# 07_-_USB_Interface.net
KiCad netlist of a schematic drawn in Altium Designer
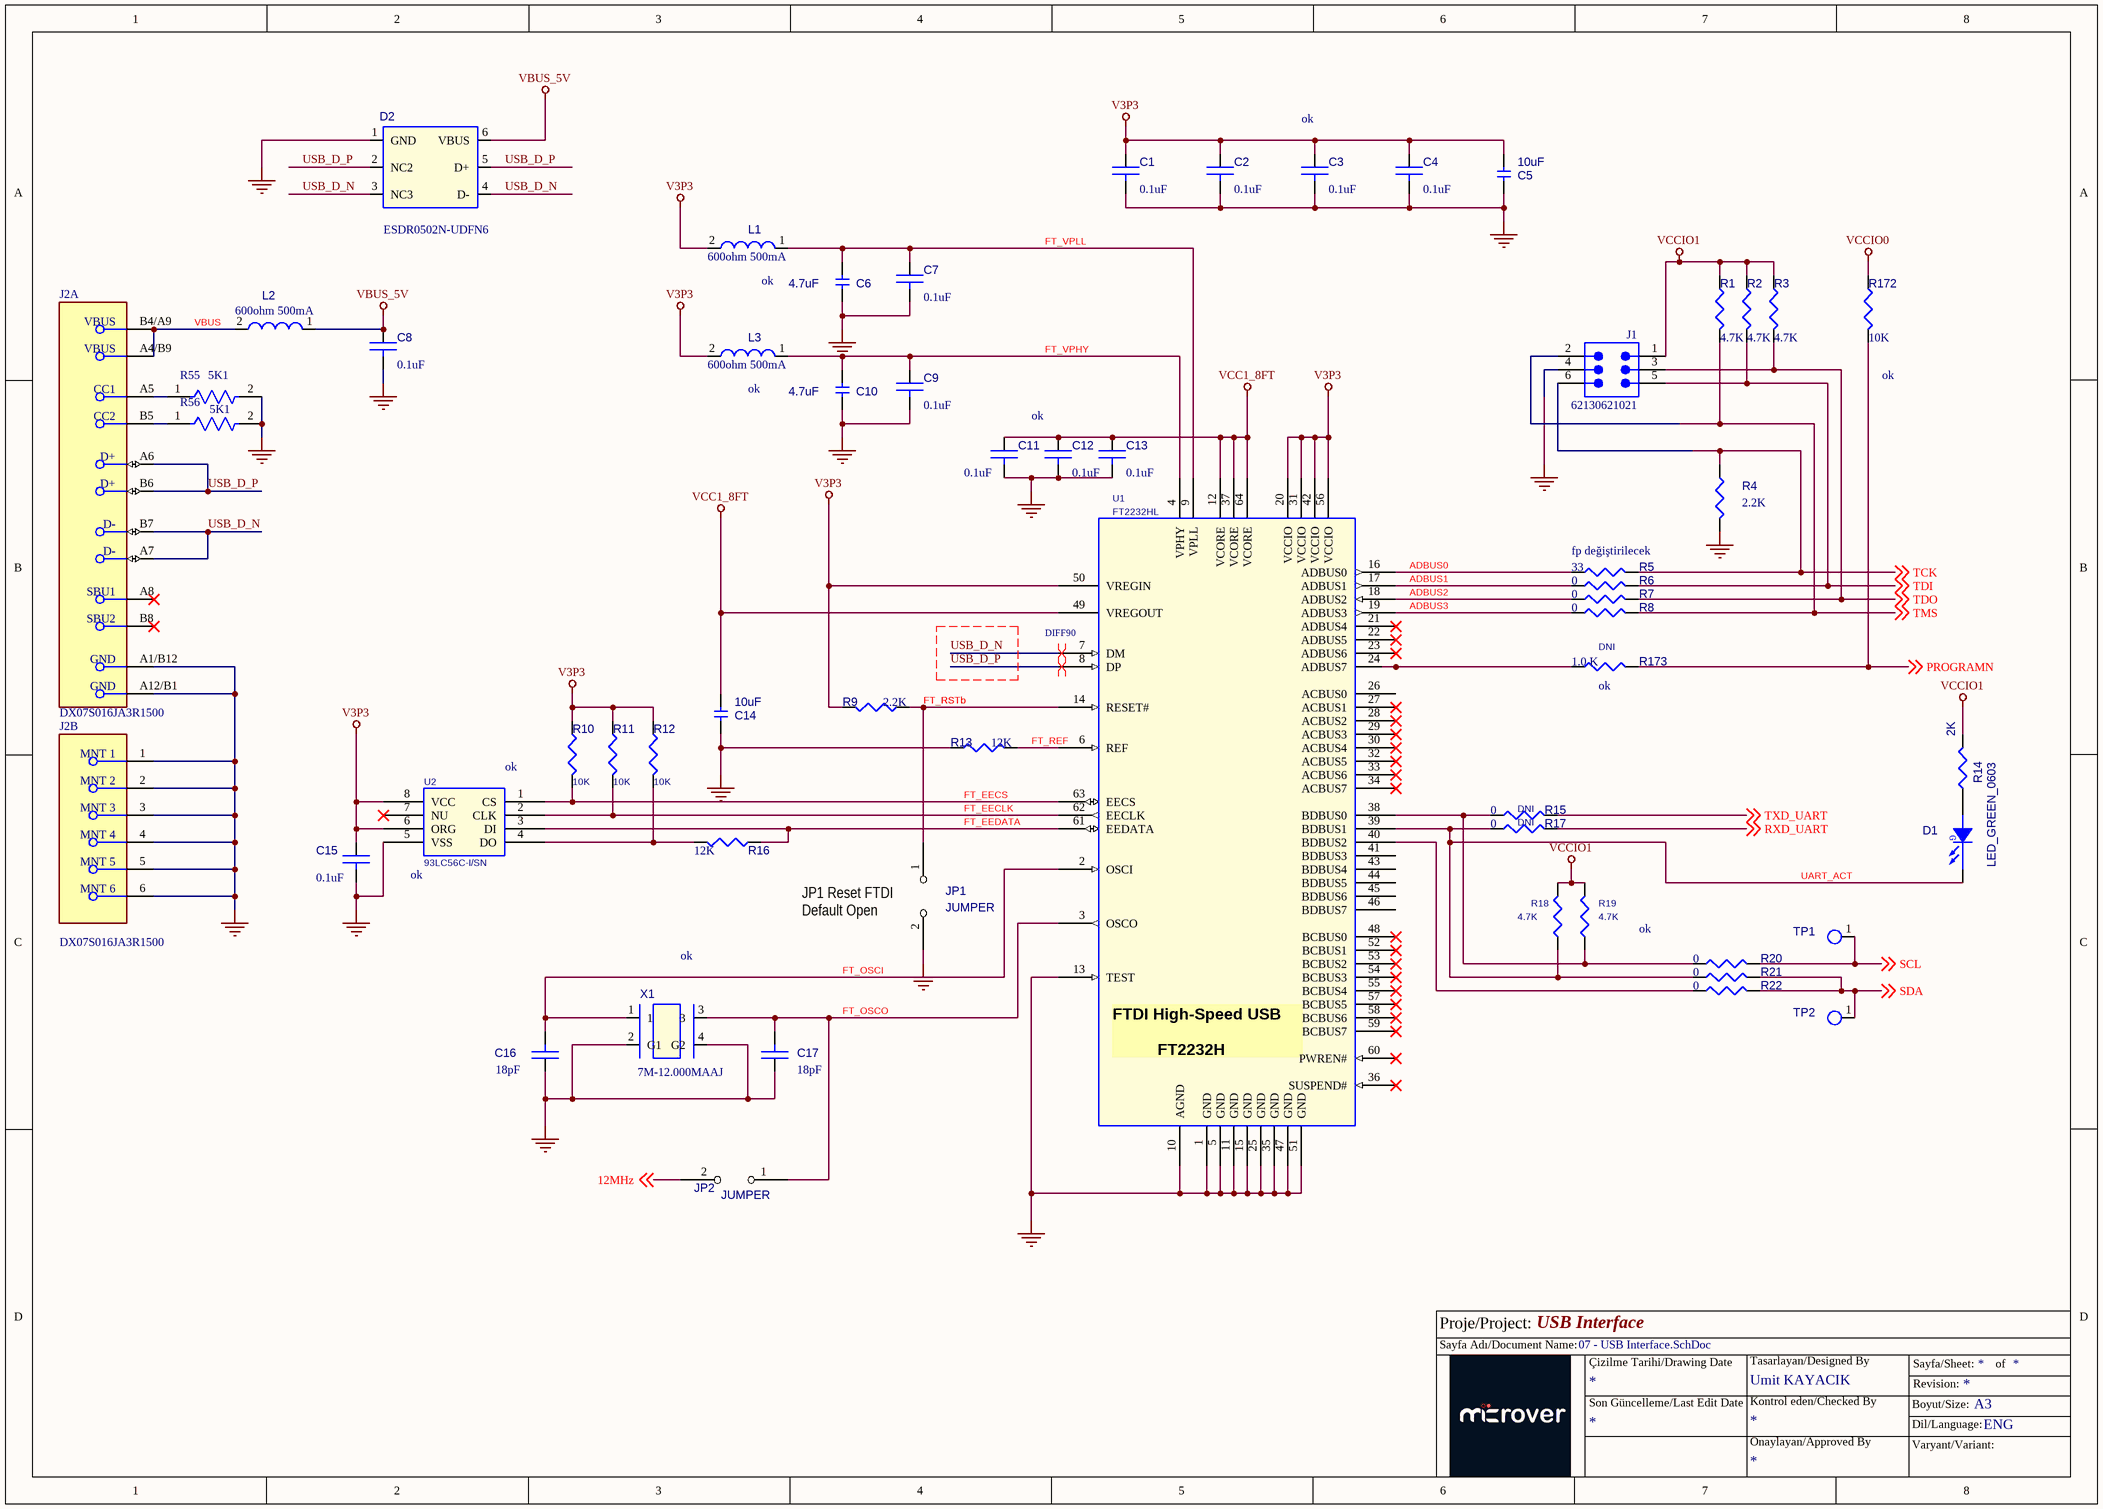
[diagram p0: 07 - USB Interface.SchDoc]

(export (version "E")
  (design (tool "Eeschema 10.0.6"))
  (components
    (comp (ref "C1")
      (value "0.1uF")
      (footprint "C0201")
      (description "CAP CER 0.1UF 25V 10% X5R 0201")
      (fields
        (field (name "MANUFACTURER") "Murata")
        (field (name "MANUFACTURER PART NUMBER") "GRM033R61E104KE14J")
      )
      (libsource (lib "*") (part "0u1_0402"))
    )
    (comp (ref "C2")
      (value "0.1uF")
      (footprint "C0201")
      (description "CAP CER 0.1UF 25V 10% X5R 0201")
      (fields
        (field (name "MANUFACTURER") "Murata")
        (field (name "MANUFACTURER PART NUMBER") "GRM033R61E104KE14J")
      )
      (libsource (lib "*") (part "0u1_0402"))
    )
    (comp (ref "C3")
      (value "0.1uF")
      (footprint "C0201")
      (description "CAP CER 0.1UF 25V 10% X5R 0201")
      (fields
        (field (name "MANUFACTURER") "Murata")
        (field (name "MANUFACTURER PART NUMBER") "GRM033R61E104KE14J")
      )
      (libsource (lib "*") (part "0u1_0402"))
    )
    (comp (ref "C4")
      (value "0.1uF")
      (footprint "C0201")
      (description "CAP CER 0.1UF 25V 10% X5R 0201")
      (fields
        (field (name "MANUFACTURER") "Murata")
        (field (name "MANUFACTURER PART NUMBER") "GRM033R61E104KE14J")
      )
      (libsource (lib "*") (part "0u1_0402"))
    )
    (comp (ref "C5")
      (value "10uF")
      (footprint "C0603")
      (fields (field (name "VOLTAGE") "CMAX"))
      (libsource (lib "*") (part "C"))
    )
    (comp (ref "C6")
      (value "4.7uF")
      (footprint "C0603")
      (fields (field (name "VOLTAGE") "CMAX"))
      (libsource (lib "*") (part "C"))
    )
    (comp (ref "C7")
      (value "0.1uF")
      (footprint "C0201")
      (description "CAP CER 0.1UF 25V 10% X5R 0201")
      (fields
        (field (name "MANUFACTURER") "Murata")
        (field (name "MANUFACTURER PART NUMBER") "GRM033R61E104KE14J")
      )
      (libsource (lib "*") (part "0u1_0402"))
    )
    (comp (ref "C8")
      (value "0.1uF")
      (footprint "C0402")
      (description "CAP CER 0.1UF 25V 10% X5R 0201")
      (fields
        (field (name "MANUFACTURER") "Murata")
        (field (name "MANUFACTURER PART NUMBER") "GRM033R61E104KE14J")
      )
      (libsource (lib "*") (part "0u1_0402"))
    )
    (comp (ref "C9")
      (value "0.1uF")
      (footprint "C0201")
      (description "CAP CER 0.1UF 25V 10% X5R 0201")
      (fields
        (field (name "MANUFACTURER") "Murata")
        (field (name "MANUFACTURER PART NUMBER") "GRM033R61E104KE14J")
      )
      (libsource (lib "*") (part "0u1_0402"))
    )
    (comp (ref "C10")
      (value "4.7uF")
      (footprint "C0603")
      (fields (field (name "VOLTAGE") "CMAX"))
      (libsource (lib "*") (part "C"))
    )
    (comp (ref "C11")
      (value "0.1uF")
      (footprint "C0201")
      (description "CAP CER 0.1UF 25V 10% X5R 0201")
      (fields
        (field (name "MANUFACTURER") "Murata")
        (field (name "MANUFACTURER PART NUMBER") "GRM033R61E104KE14J")
      )
      (libsource (lib "*") (part "0u1_0402"))
    )
    (comp (ref "C12")
      (value "0.1uF")
      (footprint "C0201")
      (description "CAP CER 0.1UF 25V 10% X5R 0201")
      (fields
        (field (name "MANUFACTURER") "Murata")
        (field (name "MANUFACTURER PART NUMBER") "GRM033R61E104KE14J")
      )
      (libsource (lib "*") (part "0u1_0402"))
    )
    (comp (ref "C13")
      (value "0.1uF")
      (footprint "c0201")
      (description "CAP CER 0.1UF 25V 10% X5R 0201")
      (fields
        (field (name "MANUFACTURER") "Murata")
        (field (name "MANUFACTURER PART NUMBER") "GRM033R61E104KE14J")
      )
      (libsource (lib "*") (part "0u1_0402"))
    )
    (comp (ref "C14")
      (value "10uF")
      (footprint "C0603")
      (fields (field (name "VOLTAGE") "CMAX"))
      (libsource (lib "*") (part "C"))
    )
    (comp (ref "C15")
      (value "0.1uF")
      (footprint "C0201")
      (description "CAP CER 0.1UF 25V 10% X5R 0201")
      (fields
        (field (name "MANUFACTURER") "Murata")
        (field (name "MANUFACTURER PART NUMBER") "GRM033R61E104KE14J")
      )
      (libsource (lib "*") (part "0u1_0402"))
    )
    (comp (ref "C16")
      (value "18pF")
      (footprint "C0402")
      (description "CAP CER 18PF 25V 10% NP0 0402")
      (fields
        (field (name "MANUFACTURER") "Kemet")
        (field (name "MANUFACTURER PART NUMBER") "C0402C180K3GACTU")
      )
      (libsource (lib "*") (part "0u1_0402"))
    )
    (comp (ref "C17")
      (value "18pF")
      (footprint "C0402")
      (description "CAP CER 18PF 25V 10% NP0 0402")
      (fields
        (field (name "MANUFACTURER") "Kemet")
        (field (name "MANUFACTURER PART NUMBER") "C0402C180K3GACTU")
      )
      (libsource (lib "*") (part "0u1_0402"))
    )
    (comp (ref "D1")
      (value "LED_GREEN_0603")
      (footprint "APT1608")
      (libsource (lib "*") (part "LED-SMT1206_GREEN_1"))
    )
    (comp (ref "D2")
      (value "ESDR0502N-UDFN6")
      (footprint "UDFN6_040")
      (description "ESD Protection - SLP2510P8 package 8-PIN")
      (fields (field (name "MFG") "Semtech"))
      (libsource (lib "*") (part "ESDR0502"))
    )
    (comp (ref "J1")
      (value "62130621021")
      (footprint "62130621021")
      (description "Conn, Pin Hdr, 6POS, 2ROW, 1.27MM Rohs Compliant: Yes")
      (libsource (lib "Altium Content Vault") (part "Header_Male_2R_06P"))
    )
    (comp (ref "J2")
      (value "DX07S016JA3R1500")
      (footprint "FP-DX07S016JA3R1500-MFG")
      (description "CONN RCP USB2.0 TYP C 24P SMD RA")
      (libsource (lib "Altium Content Vault") (part "86c7019cab7ffbad937e454fd6d8a8a"))
    )
    (comp (ref "JP1") (value "JUMPER") (footprint "R0603") (libsource (lib "*") (part "JUMPER_0")))
    (comp (ref "JP2") (value "JUMPER") (footprint "0603") (libsource (lib "*") (part "JUMPER_0")))
    (comp (ref "L1")
      (value "600ohm 500mA")
      (footprint "FB0603")
      (description "FERRITE CHIP 600 OHM 500MA 0603")
      (fields
        (field (name "MANUFACTURER") "Murata")
        (field (name "MANUFACTURER PART NUMBER") "BLM18AG601SN1D")
      )
      (libsource (lib "*") (part "FB0603"))
    )
    (comp (ref "L2")
      (value "600ohm 500mA")
      (footprint "FB0603")
      (description "FERRITE CHIP 600 OHM 500MA 0603")
      (fields
        (field (name "MANUFACTURER") "Murata")
        (field (name "MANUFACTURER PART NUMBER") "BLM18AG601SN1D")
      )
      (libsource (lib "*") (part "FB0603"))
    )
    (comp (ref "L3")
      (value "600ohm 500mA")
      (footprint "FB0603")
      (description "FERRITE CHIP 600 OHM 500MA 0603")
      (fields
        (field (name "MANUFACTURER") "Murata")
        (field (name "MANUFACTURER PART NUMBER") "BLM18AG601SN1D")
      )
      (libsource (lib "*") (part "FB0603"))
    )
    (comp (ref "R1")
      (value "4.7K")
      (footprint "R0603")
      (description "RES 4.70K OHM 1/10W 1% 0603 SMD")
      (fields
        (field (name "MANUFACTURER PART NUMBER") "CRCW06034K70FKEA")
        (field (name "MANUFACTURER") "Vishay")
      )
      (libsource (lib "*") (part "5k1_0402"))
    )
    (comp (ref "R2")
      (value "4.7K")
      (footprint "R0603")
      (description "RES 4.70K OHM 1/10W 1% 0603 SMD")
      (fields
        (field (name "MANUFACTURER PART NUMBER") "CRCW06034K70FKEA")
        (field (name "MANUFACTURER") "Vishay")
      )
      (libsource (lib "*") (part "5k1_0402"))
    )
    (comp (ref "R3")
      (value "4.7K")
      (footprint "R0603")
      (description "RES 4.70K OHM 1/10W 1% 0603 SMD")
      (fields
        (field (name "MANUFACTURER PART NUMBER") "CRCW06034K70FKEA")
        (field (name "MANUFACTURER") "Vishay")
      )
      (libsource (lib "*") (part "5k1_0402"))
    )
    (comp (ref "R4")
      (value "2.2K")
      (footprint "R0603")
      (fields
        (field (name "MANUFACTURER PART NUMBER") "CRCW06032K20FKEA")
        (field (name "MANUFACTURER") "Vishay")
      )
      (libsource (lib "*") (part "5k1_0402"))
    )
    (comp (ref "R5")
      (value "33")
      (footprint "R0402")
      (description "RES SMD 33 OHM 1% 1/10W 0402")
      (fields
        (field (name "MANUFACTURER") "Panasonic")
        (field (name "MANUFACTURER PART NUMBER") "ERJ-2RKF33R0X")
      )
      (libsource (lib "*") (part "0R_0603"))
    )
    (comp (ref "R6")
      (value "0")
      (footprint "R0603")
      (description "RES 0.0 OHM 1/10W JUMP 0603 SMD")
      (fields
        (field (name "MANUFACTURER") "Yageo")
        (field (name "MANUFACTURER PART NUMBER") "RC0603JR-070RL")
      )
      (libsource (lib "*") (part "0R_0603"))
    )
    (comp (ref "R7")
      (value "0")
      (footprint "R0603")
      (description "RES 0.0 OHM 1/10W JUMP 0603 SMD")
      (fields
        (field (name "MANUFACTURER") "Yageo")
        (field (name "MANUFACTURER PART NUMBER") "RC0603JR-070RL")
      )
      (libsource (lib "*") (part "0R_0603"))
    )
    (comp (ref "R8")
      (value "0")
      (footprint "R0603")
      (description "RES 0.0 OHM 1/10W JUMP 0603 SMD")
      (fields
        (field (name "MANUFACTURER") "Yageo")
        (field (name "MANUFACTURER PART NUMBER") "RC0603JR-070RL")
      )
      (libsource (lib "*") (part "0R_0603"))
    )
    (comp (ref "R9")
      (value "2.2K")
      (footprint "R0603")
      (fields
        (field (name "MANUFACTURER PART NUMBER") "CRCW06032K20FKEA")
        (field (name "MANUFACTURER") "Vishay")
      )
      (libsource (lib "*") (part "5k1_0402"))
    )
    (comp (ref "R10")
      (value "10K")
      (footprint "R0603")
      (description "RES 10K OHM 1/10W 5% 0603")
      (fields
        (field (name "MFG") "Stackpole Electronics Inc")
        (field (name "MANUFACTURER PART NUMBER") "RMCF0603JT10K0")
      )
      (libsource (lib "*") (part "RES_10K_1W16_0402_5P"))
    )
    (comp (ref "R11")
      (value "10K")
      (footprint "R0603")
      (description "RES 10K OHM 1/10W 5% 0603")
      (fields
        (field (name "MFG") "Stackpole Electronics Inc")
        (field (name "MANUFACTURER PART NUMBER") "RMCF0603JT10K0")
      )
      (libsource (lib "*") (part "RES_10K_1W16_0402_5P"))
    )
    (comp (ref "R12")
      (value "10K")
      (footprint "R0603")
      (description "RES 10K OHM 1/10W 5% 0603")
      (fields
        (field (name "MFG") "Stackpole Electronics Inc")
        (field (name "MANUFACTURER PART NUMBER") "RMCF0603JT10K0")
      )
      (libsource (lib "*") (part "RES_10K_1W16_0402_5P"))
    )
    (comp (ref "R13")
      (value "12K")
      (footprint "R0603")
      (description "RES 12K OHM 1/10W 1% 0603 SMD")
      (fields
        (field (name "MANUFACTURER") "Yageo")
        (field (name "MANUFACTURER PART NUMBER") "RC0603FR-0712KL")
      )
      (libsource (lib "*") (part "10k_0402"))
    )
    (comp (ref "R14") (value "2K") (footprint "R0402") (libsource (lib "*") (part "RES_0")))
    (comp (ref "R15")
      (value "0")
      (footprint "R0603")
      (description "Res 1/10W 0.0 Ohm 5% 0603")
      (fields
        (field (name "MANUFACTURER") "Yageo")
        (field (name "MANUFACTURER PART NUMBER") "RC0603JR-070RL")
        (field (name "ASSY") "DNI")
      )
      (libsource (lib "*") (part "0R_0603"))
    )
    (comp (ref "R16")
      (value "12K")
      (footprint "R0603")
      (description "RES 12K OHM 1/10W 1% 0603 SMD")
      (fields
        (field (name "MANUFACTURER") "Yageo")
        (field (name "MANUFACTURER PART NUMBER") "RC0603FR-0712KL")
      )
      (libsource (lib "*") (part "10k_0402"))
    )
    (comp (ref "R17")
      (value "0")
      (footprint "R0603")
      (description "Res 1/10W 0.0 Ohm 5% 0603")
      (fields
        (field (name "MANUFACTURER") "Yageo")
        (field (name "MANUFACTURER PART NUMBER") "RC0603JR-070RL")
        (field (name "ASSY") "DNI")
      )
      (libsource (lib "*") (part "0R_0603"))
    )
    (comp (ref "R18") (value "4.7K") (footprint "RLP-101") (libsource (lib "*") (part "RESISTOR")))
    (comp (ref "R19") (value "4.7K") (footprint "RLP-101") (libsource (lib "*") (part "RESISTOR")))
    (comp (ref "R20")
      (value "0")
      (footprint "R0603")
      (description "RES 0.0 OHM 1/10W JUMP 0603 SMD")
      (fields
        (field (name "MANUFACTURER") "Yageo")
        (field (name "MANUFACTURER PART NUMBER") "RC0603JR-070RL")
      )
      (libsource (lib "*") (part "0R_0603"))
    )
    (comp (ref "R21")
      (value "0")
      (footprint "R0603")
      (description "RES 0.0 OHM 1/10W JUMP 0603 SMD")
      (fields
        (field (name "MANUFACTURER") "Yageo")
        (field (name "MANUFACTURER PART NUMBER") "RC0603JR-070RL")
      )
      (libsource (lib "*") (part "0R_0603"))
    )
    (comp (ref "R22")
      (value "0")
      (footprint "R0603")
      (description "RES 0.0 OHM 1/10W JUMP 0603 SMD")
      (fields
        (field (name "MANUFACTURER") "Yageo")
        (field (name "MANUFACTURER PART NUMBER") "RC0603JR-070RL")
      )
      (libsource (lib "*") (part "0R_0603"))
    )
    (comp (ref "R55")
      (value "5K1")
      (footprint "FP-CR0402-IPC_A")
      (description "Thick Film Chip Resistors 0402 5.1kΩ 0.0625W 1% 100ppm/°C")
      (fields (field (name "TOLERANCE") "1%"))
      (libsource (lib "Altium Content Vault") (part "1029c3af85768c4190bb7ad29bc67b5"))
    )
    (comp (ref "R56")
      (value "5K1")
      (footprint "FP-CR0402-IPC_A")
      (description "Thick Film Chip Resistors 0402 5.1kΩ 0.0625W 1% 100ppm/°C")
      (fields (field (name "TOLERANCE") "1%"))
      (libsource (lib "Altium Content Vault") (part "1029c3af85768c4190bb7ad29bc67b5"))
    )
    (comp (ref "R172")
      (value "10K")
      (footprint "R0603")
      (description "RES SMD 10K OHM 1% 1/10W 0603")
      (fields
        (field (name "MANUFACTURER PART NUMBER") "RC0603FR-0710KL")
        (field (name "MANUFACTURER") "Yageo")
      )
      (libsource (lib "*") (part "5k1_0402"))
    )
    (comp (ref "R173")
      (value "1.0 K")
      (footprint "R0603")
      (description "RES SMD 1K OHM 1% 1/10W 0603")
      (fields
        (field (name "MANUFACTURER") "Yageo")
        (field (name "MANUFACTURER PART NUMBER") "RC0603FR-071KL")
        (field (name "ASSY") "DNI")
      )
      (libsource (lib "*") (part "0R_0603"))
    )
    (comp (ref "TP1")
      (value "TP_S_40_63")
      (footprint "TP_1MM")
      (description "Square test point, 40mil inner diameter, 63mil outer diameter")
      (libsource (lib "*") (part "TP_S_40_63"))
    )
    (comp (ref "TP2")
      (value "TP_S_40_63")
      (footprint "TP_1MM")
      (description "Square test point, 40mil inner diameter, 63mil outer diameter")
      (libsource (lib "*") (part "TP_S_40_63"))
    )
    (comp (ref "U1")
      (value "FT2232HL")
      (footprint "tqfp64_0p5_12p2x12p2_h1p6")
      (description "IC USB HS DUAL UART/FIFO 64-LQFP")
      (fields (field (name "MANUFACTURER") "FTDI"))
      (libsource (lib "*") (part "FT2232HL"))
    )
    (comp (ref "U2")
      (value "93LC56C-I/SN")
      (footprint "so8_50_244")
      (description "IC EEPROM 2KBIT 3MHZ 8SOIC")
      (fields (field (name "MANUFACTURER") "Microchip"))
      (libsource (lib "*") (part "93LC56_SO8_0"))
    )
    (comp (ref "X1")
      (value "7M-12.000MAAJ")
      (footprint "xtal_4p_7m")
      (description "CRYSTAL 12MHZ 18PF SMD")
      (fields (field (name "MANUFACTURER PART NUMBER") "7M-12.000MAAJ-T") (field (name "MANUFACTURER") "TXC"))
      (libsource (lib "*") (part "crystal-3p2x2p5"))
    )
  )
  (nets
    (net (code "1") (name "/ADBUS0") (class "Default")
      (node (ref "R5") (pin "1") (pinfunction "1_1") (pintype "passive"))
      (node (ref "U1") (pin "16") (pinfunction "ADBUS0_16") (pintype "output"))
    )
    (net (code "2") (name "/ADBUS1") (class "Default")
      (node (ref "R6") (pin "1") (pinfunction "1_1") (pintype "passive"))
      (node (ref "U1") (pin "17") (pinfunction "ADBUS1_17") (pintype "output"))
    )
    (net (code "3") (name "/ADBUS2") (class "Default")
      (node (ref "R7") (pin "1") (pinfunction "1_1") (pintype "passive"))
      (node (ref "U1") (pin "18") (pinfunction "ADBUS2_18") (pintype "input"))
    )
    (net (code "4") (name "/ADBUS3") (class "Default")
      (node (ref "R8") (pin "1") (pinfunction "1_1") (pintype "passive"))
      (node (ref "U1") (pin "19") (pinfunction "ADBUS3_19") (pintype "output"))
    )
    (net (code "5") (name "/FT_EECLK") (class "Default")
      (node (ref "R11") (pin "2") (pinfunction "2_2") (pintype "passive"))
      (node (ref "U1") (pin "62") (pinfunction "EECLK_62") (pintype "output"))
      (node (ref "U2") (pin "2") (pinfunction "CLK_2") (pintype "passive"))
    )
    (net (code "6") (name "/FT_EECS") (class "Default")
      (node (ref "R10") (pin "2") (pinfunction "2_2") (pintype "passive"))
      (node (ref "U1") (pin "63") (pinfunction "EECS_63") (pintype "bidirectional"))
      (node (ref "U2") (pin "1") (pinfunction "CS_1") (pintype "passive"))
    )
    (net (code "7") (name "/FT_EEDATA") (class "Default")
      (node (ref "R16") (pin "1") (pinfunction "1_1") (pintype "passive"))
      (node (ref "U1") (pin "61") (pinfunction "EEDATA_61") (pintype "bidirectional"))
      (node (ref "U2") (pin "3") (pinfunction "DI_3") (pintype "passive"))
    )
    (net (code "8") (name "/FT_OSCI") (class "Default")
      (node (ref "C16") (pin "2") (pinfunction "2_2") (pintype "passive"))
      (node (ref "U1") (pin "2") (pinfunction "OSCI_2") (pintype "input"))
      (node (ref "X1") (pin "1") (pinfunction "1_1") (pintype "passive"))
    )
    (net (code "9") (name "/FT_OSCO") (class "Default")
      (node (ref "C17") (pin "2") (pinfunction "2_2") (pintype "passive"))
      (node (ref "JP2") (pin "1") (pinfunction "1_1") (pintype "passive"))
      (node (ref "U1") (pin "3") (pinfunction "OSCO_3") (pintype "output"))
      (node (ref "X1") (pin "3") (pinfunction "3_3") (pintype "passive"))
    )
    (net (code "10") (name "/FT_REF") (class "Default")
      (node (ref "R13") (pin "2") (pinfunction "2_2") (pintype "passive"))
      (node (ref "U1") (pin "6") (pinfunction "REF_6") (pintype "input"))
    )
    (net (code "11") (name "/FT_RSTb") (class "Default")
      (node (ref "JP1") (pin "1") (pinfunction "1_1") (pintype "passive"))
      (node (ref "R9") (pin "1") (pinfunction "1_1") (pintype "passive"))
      (node (ref "U1") (pin "14") (pinfunction "RESET#_14") (pintype "input"))
    )
    (net (code "12") (name "/FT_VPHY") (class "Default")
      (node (ref "C10") (pin "2") (pinfunction "2_2") (pintype "passive"))
      (node (ref "C9") (pin "1") (pinfunction "1_1") (pintype "passive"))
      (node (ref "L3") (pin "1") (pinfunction "1_1") (pintype "passive"))
      (node (ref "U1") (pin "4") (pinfunction "VPHY_4") (pintype "power_in"))
    )
    (net (code "13") (name "/FT_VPLL") (class "Default")
      (node (ref "C6") (pin "2") (pinfunction "2_2") (pintype "passive"))
      (node (ref "C7") (pin "1") (pinfunction "1_1") (pintype "passive"))
      (node (ref "L1") (pin "1") (pinfunction "1_1") (pintype "passive"))
      (node (ref "U1") (pin "9") (pinfunction "VPLL_9") (pintype "power_in"))
    )
    (net (code "14") (name "/UART_ACT") (class "Default")
      (node (ref "D1") (pin "1") (pinfunction "CATHODE_1") (pintype "passive"))
      (node (ref "R17") (pin "1") (pinfunction "1_1") (pintype "passive"))
      (node (ref "R18") (pin "1") (pinfunction "1_1") (pintype "passive"))
      (node (ref "R21") (pin "1") (pinfunction "1_1") (pintype "passive"))
      (node (ref "U1") (pin "39") (pinfunction "BDBUS1_39") (pintype "passive"))
    )
    (net (code "15") (name "/USB_D_N") (class "Default")
      (node (ref "D2") (pin "3") (pinfunction "NC3_3") (pintype "passive"))
      (node (ref "D2") (pin "4") (pinfunction "D-_4") (pintype "passive"))
      (node (ref "J2") (pin "A7") (pinfunction "D-_A7") (pintype "bidirectional"))
      (node (ref "J2") (pin "B7") (pinfunction "D-_B7") (pintype "bidirectional"))
      (node (ref "U1") (pin "7") (pinfunction "DM_7") (pintype "input"))
    )
    (net (code "16") (name "/USB_D_P") (class "Default")
      (node (ref "D2") (pin "2") (pinfunction "NC2_2") (pintype "passive"))
      (node (ref "D2") (pin "5") (pinfunction "D+_5") (pintype "passive"))
      (node (ref "J2") (pin "A6") (pinfunction "D+_A6") (pintype "bidirectional"))
      (node (ref "J2") (pin "B6") (pinfunction "D+_B6") (pintype "bidirectional"))
      (node (ref "U1") (pin "8") (pinfunction "DP_8") (pintype "input"))
    )
    (net (code "17") (name "/VBUS") (class "Default")
      (node (ref "J2") (pin "A4/B9") (pinfunction "VBUS_A4/B9") (pintype "power_in"))
      (node (ref "J2") (pin "B4/A9") (pinfunction "VBUS_B4/A9") (pintype "power_in"))
      (node (ref "L2") (pin "2") (pinfunction "2_2") (pintype "passive"))
    )
    (net (code "18") (name "12MHz") (class "Default")
      (node (ref "JP2") (pin "2") (pinfunction "2_2") (pintype "passive"))
    )
    (net (code "19") (name "GND") (class "Default")
      (node (ref "C1") (pin "2") (pinfunction "2_2") (pintype "passive"))
      (node (ref "C10") (pin "1") (pinfunction "1_1") (pintype "passive"))
      (node (ref "C11") (pin "2") (pinfunction "2_2") (pintype "passive"))
      (node (ref "C12") (pin "2") (pinfunction "2_2") (pintype "passive"))
      (node (ref "C13") (pin "2") (pinfunction "2_2") (pintype "passive"))
      (node (ref "C14") (pin "1") (pinfunction "1_1") (pintype "passive"))
      (node (ref "C15") (pin "2") (pinfunction "2_2") (pintype "passive"))
      (node (ref "C16") (pin "1") (pinfunction "1_1") (pintype "passive"))
      (node (ref "C17") (pin "1") (pinfunction "1_1") (pintype "passive"))
      (node (ref "C2") (pin "2") (pinfunction "2_2") (pintype "passive"))
      (node (ref "C3") (pin "2") (pinfunction "2_2") (pintype "passive"))
      (node (ref "C4") (pin "2") (pinfunction "2_2") (pintype "passive"))
      (node (ref "C5") (pin "1") (pinfunction "1_1") (pintype "passive"))
      (node (ref "C6") (pin "1") (pinfunction "1_1") (pintype "passive"))
      (node (ref "C7") (pin "2") (pinfunction "2_2") (pintype "passive"))
      (node (ref "C8") (pin "2") (pinfunction "2_2") (pintype "passive"))
      (node (ref "C9") (pin "2") (pinfunction "2_2") (pintype "passive"))
      (node (ref "D2") (pin "1") (pinfunction "GND_1") (pintype "passive"))
      (node (ref "J1") (pin "4") (pinfunction "4_4") (pintype "passive"))
      (node (ref "J2") (pin "1") (pinfunction "MNT_1_1") (pintype "passive"))
      (node (ref "J2") (pin "2") (pinfunction "MNT_2_2") (pintype "passive"))
      (node (ref "J2") (pin "3") (pinfunction "MNT_3_3") (pintype "passive"))
      (node (ref "J2") (pin "4") (pinfunction "MNT_4_4") (pintype "passive"))
      (node (ref "J2") (pin "5") (pinfunction "MNT_5_5") (pintype "passive"))
      (node (ref "J2") (pin "6") (pinfunction "MNT_6_6") (pintype "passive"))
      (node (ref "J2") (pin "A1/B12") (pinfunction "GND_A1/B12") (pintype "power_in"))
      (node (ref "J2") (pin "A12/B1") (pinfunction "GND_A12/B1") (pintype "power_in"))
      (node (ref "JP1") (pin "2") (pinfunction "2_2") (pintype "passive"))
      (node (ref "R13") (pin "1") (pinfunction "1_1") (pintype "passive"))
      (node (ref "R4") (pin "2") (pinfunction "2_2") (pintype "passive"))
      (node (ref "R55") (pin "2") (pinfunction "2_2") (pintype "passive"))
      (node (ref "R56") (pin "2") (pinfunction "2_2") (pintype "passive"))
      (node (ref "U1") (pin "1") (pinfunction "GND_1") (pintype "power_in"))
      (node (ref "U1") (pin "10") (pinfunction "AGND_10") (pintype "power_in"))
      (node (ref "U1") (pin "11") (pinfunction "GND_11") (pintype "power_in"))
      (node (ref "U1") (pin "13") (pinfunction "TEST_13") (pintype "input"))
      (node (ref "U1") (pin "15") (pinfunction "GND_15") (pintype "power_in"))
      (node (ref "U1") (pin "25") (pinfunction "GND_25") (pintype "power_in"))
      (node (ref "U1") (pin "35") (pinfunction "GND_35") (pintype "power_in"))
      (node (ref "U1") (pin "47") (pinfunction "GND_47") (pintype "power_in"))
      (node (ref "U1") (pin "5") (pinfunction "GND_5") (pintype "power_in"))
      (node (ref "U1") (pin "51") (pinfunction "GND_51") (pintype "power_in"))
      (node (ref "U2") (pin "5") (pinfunction "VSS_5") (pintype "power_in"))
      (node (ref "X1") (pin "2") (pinfunction "G1_2") (pintype "passive"))
      (node (ref "X1") (pin "4") (pinfunction "G2_4") (pintype "passive"))
    )
    (net (code "20") (name "Net-(D1-ANODE)") (class "Default")
      (node (ref "D1") (pin "2") (pinfunction "ANODE_2") (pintype "passive"))
      (node (ref "R14") (pin "1") (pinfunction "1_1") (pintype "passive"))
    )
    (net (code "21") (name "Net-(J2A-CC1)") (class "Default")
      (node (ref "J2") (pin "A5") (pinfunction "CC1_A5") (pintype "passive"))
      (node (ref "R55") (pin "1") (pinfunction "1_1") (pintype "passive"))
    )
    (net (code "22") (name "Net-(J2A-CC2)") (class "Default")
      (node (ref "J2") (pin "B5") (pinfunction "CC2_B5") (pintype "passive"))
      (node (ref "R56") (pin "1") (pinfunction "1_1") (pintype "passive"))
    )
    (net (code "23") (name "Net-(U1-ADBUS7)") (class "Default")
      (node (ref "R173") (pin "1") (pinfunction "1_1") (pintype "passive"))
      (node (ref "U1") (pin "24") (pinfunction "ADBUS7_24") (pintype "passive"))
    )
    (net (code "24") (name "Net-(U1-BDBUS0)") (class "Default")
      (node (ref "R15") (pin "1") (pinfunction "1_1") (pintype "passive"))
      (node (ref "R19") (pin "1") (pinfunction "1_1") (pintype "passive"))
      (node (ref "R20") (pin "1") (pinfunction "1_1") (pintype "passive"))
      (node (ref "U1") (pin "38") (pinfunction "BDBUS0_38") (pintype "passive"))
    )
    (net (code "25") (name "Net-(U1-BDBUS2)") (class "Default")
      (node (ref "R22") (pin "1") (pinfunction "1_1") (pintype "passive"))
      (node (ref "U1") (pin "40") (pinfunction "BDBUS2_40") (pintype "passive"))
    )
    (net (code "26") (name "Net-(U2-DO)") (class "Default")
      (node (ref "R12") (pin "2") (pinfunction "2_2") (pintype "passive"))
      (node (ref "R16") (pin "2") (pinfunction "2_2") (pintype "passive"))
      (node (ref "U2") (pin "4") (pinfunction "DO_4") (pintype "passive"))
    )
    (net (code "27") (name "PROGRAMN") (class "Default")
      (node (ref "R172") (pin "2") (pinfunction "2_2") (pintype "passive"))
      (node (ref "R173") (pin "2") (pinfunction "2_2") (pintype "passive"))
    )
    (net (code "28") (name "RXD_UART") (class "Default")
      (node (ref "R17") (pin "2") (pinfunction "2_2") (pintype "passive"))
    )
    (net (code "29") (name "SCL") (class "Default")
      (node (ref "R20") (pin "2") (pinfunction "2_2") (pintype "passive"))
      (node (ref "TP1") (pin "1") (pinfunction "TP_1") (pintype "passive"))
    )
    (net (code "30") (name "SDA") (class "Default")
      (node (ref "R21") (pin "2") (pinfunction "2_2") (pintype "passive"))
      (node (ref "R22") (pin "2") (pinfunction "2_2") (pintype "passive"))
      (node (ref "TP2") (pin "1") (pinfunction "TP_1") (pintype "passive"))
    )
    (net (code "31") (name "TCK") (class "Default")
      (node (ref "J1") (pin "6") (pinfunction "6_6") (pintype "passive"))
      (node (ref "R4") (pin "1") (pinfunction "1_1") (pintype "passive"))
      (node (ref "R5") (pin "2") (pinfunction "2_2") (pintype "passive"))
    )
    (net (code "32") (name "TDI") (class "Default")
      (node (ref "J1") (pin "5") (pinfunction "5_5") (pintype "passive"))
      (node (ref "R2") (pin "2") (pinfunction "2_2") (pintype "passive"))
      (node (ref "R6") (pin "2") (pinfunction "2_2") (pintype "passive"))
    )
    (net (code "33") (name "TDO") (class "Default")
      (node (ref "J1") (pin "3") (pinfunction "3_3") (pintype "passive"))
      (node (ref "R3") (pin "2") (pinfunction "2_2") (pintype "passive"))
      (node (ref "R7") (pin "2") (pinfunction "2_2") (pintype "passive"))
    )
    (net (code "34") (name "TMS") (class "Default")
      (node (ref "J1") (pin "2") (pinfunction "2_2") (pintype "passive"))
      (node (ref "R1") (pin "2") (pinfunction "2_2") (pintype "passive"))
      (node (ref "R8") (pin "2") (pinfunction "2_2") (pintype "passive"))
    )
    (net (code "35") (name "TXD_UART") (class "Default")
      (node (ref "R15") (pin "2") (pinfunction "2_2") (pintype "passive"))
    )
    (net (code "36") (name "V3P3") (class "Default")
      (node (ref "C1") (pin "1") (pinfunction "1_1") (pintype "passive"))
      (node (ref "C15") (pin "1") (pinfunction "1_1") (pintype "passive"))
      (node (ref "C2") (pin "1") (pinfunction "1_1") (pintype "passive"))
      (node (ref "C3") (pin "1") (pinfunction "1_1") (pintype "passive"))
      (node (ref "C4") (pin "1") (pinfunction "1_1") (pintype "passive"))
      (node (ref "C5") (pin "2") (pinfunction "2_2") (pintype "passive"))
      (node (ref "L1") (pin "2") (pinfunction "2_2") (pintype "passive"))
      (node (ref "L3") (pin "2") (pinfunction "2_2") (pintype "passive"))
      (node (ref "R10") (pin "1") (pinfunction "1_1") (pintype "passive"))
      (node (ref "R11") (pin "1") (pinfunction "1_1") (pintype "passive"))
      (node (ref "R12") (pin "1") (pinfunction "1_1") (pintype "passive"))
      (node (ref "R9") (pin "2") (pinfunction "2_2") (pintype "passive"))
      (node (ref "U1") (pin "20") (pinfunction "VCCIO_20") (pintype "power_in"))
      (node (ref "U1") (pin "31") (pinfunction "VCCIO_31") (pintype "power_in"))
      (node (ref "U1") (pin "42") (pinfunction "VCCIO_42") (pintype "power_in"))
      (node (ref "U1") (pin "50") (pinfunction "VREGIN_50") (pintype "power_in"))
      (node (ref "U1") (pin "56") (pinfunction "VCCIO_56") (pintype "power_in"))
      (node (ref "U2") (pin "6") (pinfunction "ORG_6") (pintype "passive"))
      (node (ref "U2") (pin "8") (pinfunction "VCC_8") (pintype "power_in"))
    )
    (net (code "37") (name "VBUS_5V") (class "Default")
      (node (ref "C8") (pin "1") (pinfunction "1_1") (pintype "passive"))
      (node (ref "D2") (pin "6") (pinfunction "VBUS_6") (pintype "passive"))
      (node (ref "L2") (pin "1") (pinfunction "1_1") (pintype "passive"))
    )
    (net (code "38") (name "VCC1_8FT") (class "Default")
      (node (ref "C11") (pin "1") (pinfunction "1_1") (pintype "passive"))
      (node (ref "C12") (pin "1") (pinfunction "1_1") (pintype "passive"))
      (node (ref "C13") (pin "1") (pinfunction "1_1") (pintype "passive"))
      (node (ref "C14") (pin "2") (pinfunction "2_2") (pintype "passive"))
      (node (ref "U1") (pin "12") (pinfunction "VCORE_12") (pintype "power_in"))
      (node (ref "U1") (pin "37") (pinfunction "VCORE_37") (pintype "power_in"))
      (node (ref "U1") (pin "49") (pinfunction "VREGOUT_49") (pintype "power_in"))
      (node (ref "U1") (pin "64") (pinfunction "VCORE_64") (pintype "power_in"))
    )
    (net (code "39") (name "VCCIO0") (class "Default")
      (node (ref "R172") (pin "1") (pinfunction "1_1") (pintype "passive"))
    )
    (net (code "40") (name "VCCIO1") (class "Default")
      (node (ref "J1") (pin "1") (pinfunction "1_1") (pintype "passive"))
      (node (ref "R1") (pin "1") (pinfunction "1_1") (pintype "passive"))
      (node (ref "R14") (pin "2") (pinfunction "2_2") (pintype "passive"))
      (node (ref "R18") (pin "2") (pinfunction "2_2") (pintype "passive"))
      (node (ref "R19") (pin "2") (pinfunction "2_2") (pintype "passive"))
      (node (ref "R2") (pin "1") (pinfunction "1_1") (pintype "passive"))
      (node (ref "R3") (pin "1") (pinfunction "1_1") (pintype "passive"))
    )
    (net (code "41") (name "unconnected-(J2A-SBU1-PadA8)") (class "Default")
      (node (ref "J2") (pin "A8") (pinfunction "SBU1_A8") (pintype "passive+no_connect"))
    )
    (net (code "42") (name "unconnected-(J2A-SBU2-PadB8)") (class "Default")
      (node (ref "J2") (pin "B8") (pinfunction "SBU2_B8") (pintype "passive+no_connect"))
    )
    (net (code "43") (name "unconnected-(U1-ACBUS0-Pad26)") (class "Default")
      (node (ref "U1") (pin "26") (pinfunction "ACBUS0_26") (pintype "passive"))
    )
    (net (code "44") (name "unconnected-(U1-ACBUS1-Pad27)") (class "Default")
      (node (ref "U1") (pin "27") (pinfunction "ACBUS1_27") (pintype "passive+no_connect"))
    )
    (net (code "45") (name "unconnected-(U1-ACBUS2-Pad28)") (class "Default")
      (node (ref "U1") (pin "28") (pinfunction "ACBUS2_28") (pintype "passive+no_connect"))
    )
    (net (code "46") (name "unconnected-(U1-ACBUS3-Pad29)") (class "Default")
      (node (ref "U1") (pin "29") (pinfunction "ACBUS3_29") (pintype "passive+no_connect"))
    )
    (net (code "47") (name "unconnected-(U1-ACBUS4-Pad30)") (class "Default")
      (node (ref "U1") (pin "30") (pinfunction "ACBUS4_30") (pintype "passive+no_connect"))
    )
    (net (code "48") (name "unconnected-(U1-ACBUS5-Pad32)") (class "Default")
      (node (ref "U1") (pin "32") (pinfunction "ACBUS5_32") (pintype "passive+no_connect"))
    )
    (net (code "49") (name "unconnected-(U1-ACBUS6-Pad33)") (class "Default")
      (node (ref "U1") (pin "33") (pinfunction "ACBUS6_33") (pintype "passive+no_connect"))
    )
    (net (code "50") (name "unconnected-(U1-ACBUS7-Pad34)") (class "Default")
      (node (ref "U1") (pin "34") (pinfunction "ACBUS7_34") (pintype "passive+no_connect"))
    )
    (net (code "51") (name "unconnected-(U1-ADBUS4-Pad21)") (class "Default")
      (node (ref "U1") (pin "21") (pinfunction "ADBUS4_21") (pintype "passive+no_connect"))
    )
    (net (code "52") (name "unconnected-(U1-ADBUS5-Pad22)") (class "Default")
      (node (ref "U1") (pin "22") (pinfunction "ADBUS5_22") (pintype "passive+no_connect"))
    )
    (net (code "53") (name "unconnected-(U1-ADBUS6-Pad23)") (class "Default")
      (node (ref "U1") (pin "23") (pinfunction "ADBUS6_23") (pintype "passive+no_connect"))
    )
    (net (code "54") (name "unconnected-(U1-BCBUS0-Pad48)") (class "Default")
      (node (ref "U1") (pin "48") (pinfunction "BCBUS0_48") (pintype "passive+no_connect"))
    )
    (net (code "55") (name "unconnected-(U1-BCBUS1-Pad52)") (class "Default")
      (node (ref "U1") (pin "52") (pinfunction "BCBUS1_52") (pintype "passive+no_connect"))
    )
    (net (code "56") (name "unconnected-(U1-BCBUS2-Pad53)") (class "Default")
      (node (ref "U1") (pin "53") (pinfunction "BCBUS2_53") (pintype "passive+no_connect"))
    )
    (net (code "57") (name "unconnected-(U1-BCBUS3-Pad54)") (class "Default")
      (node (ref "U1") (pin "54") (pinfunction "BCBUS3_54") (pintype "passive+no_connect"))
    )
    (net (code "58") (name "unconnected-(U1-BCBUS4-Pad55)") (class "Default")
      (node (ref "U1") (pin "55") (pinfunction "BCBUS4_55") (pintype "passive+no_connect"))
    )
    (net (code "59") (name "unconnected-(U1-BCBUS5-Pad57)") (class "Default")
      (node (ref "U1") (pin "57") (pinfunction "BCBUS5_57") (pintype "passive+no_connect"))
    )
    (net (code "60") (name "unconnected-(U1-BCBUS6-Pad58)") (class "Default")
      (node (ref "U1") (pin "58") (pinfunction "BCBUS6_58") (pintype "passive+no_connect"))
    )
    (net (code "61") (name "unconnected-(U1-BCBUS7-Pad59)") (class "Default")
      (node (ref "U1") (pin "59") (pinfunction "BCBUS7_59") (pintype "passive+no_connect"))
    )
    (net (code "62") (name "unconnected-(U1-BDBUS3-Pad41)") (class "Default")
      (node (ref "U1") (pin "41") (pinfunction "BDBUS3_41") (pintype "passive"))
    )
    (net (code "63") (name "unconnected-(U1-BDBUS4-Pad43)") (class "Default")
      (node (ref "U1") (pin "43") (pinfunction "BDBUS4_43") (pintype "passive"))
    )
    (net (code "64") (name "unconnected-(U1-BDBUS5-Pad44)") (class "Default")
      (node (ref "U1") (pin "44") (pinfunction "BDBUS5_44") (pintype "passive"))
    )
    (net (code "65") (name "unconnected-(U1-BDBUS6-Pad45)") (class "Default")
      (node (ref "U1") (pin "45") (pinfunction "BDBUS6_45") (pintype "passive"))
    )
    (net (code "66") (name "unconnected-(U1-BDBUS7-Pad46)") (class "Default")
      (node (ref "U1") (pin "46") (pinfunction "BDBUS7_46") (pintype "passive"))
    )
    (net (code "67") (name "unconnected-(U1-PWREN#-Pad60)") (class "Default")
      (node (ref "U1") (pin "60") (pinfunction "PWREN#_60") (pintype "input+no_connect"))
    )
    (net (code "68") (name "unconnected-(U1-SUSPEND#-Pad36)") (class "Default")
      (node (ref "U1") (pin "36") (pinfunction "SUSPEND#_36") (pintype "input+no_connect"))
    )
    (net (code "69") (name "unconnected-(U2-NU-Pad7)") (class "Default")
      (node (ref "U2") (pin "7") (pinfunction "NU_7") (pintype "passive+no_connect"))
    )
  )
)
